# DifferentialPair.net
KiCad netlist of a schematic drawn in Altium Designer
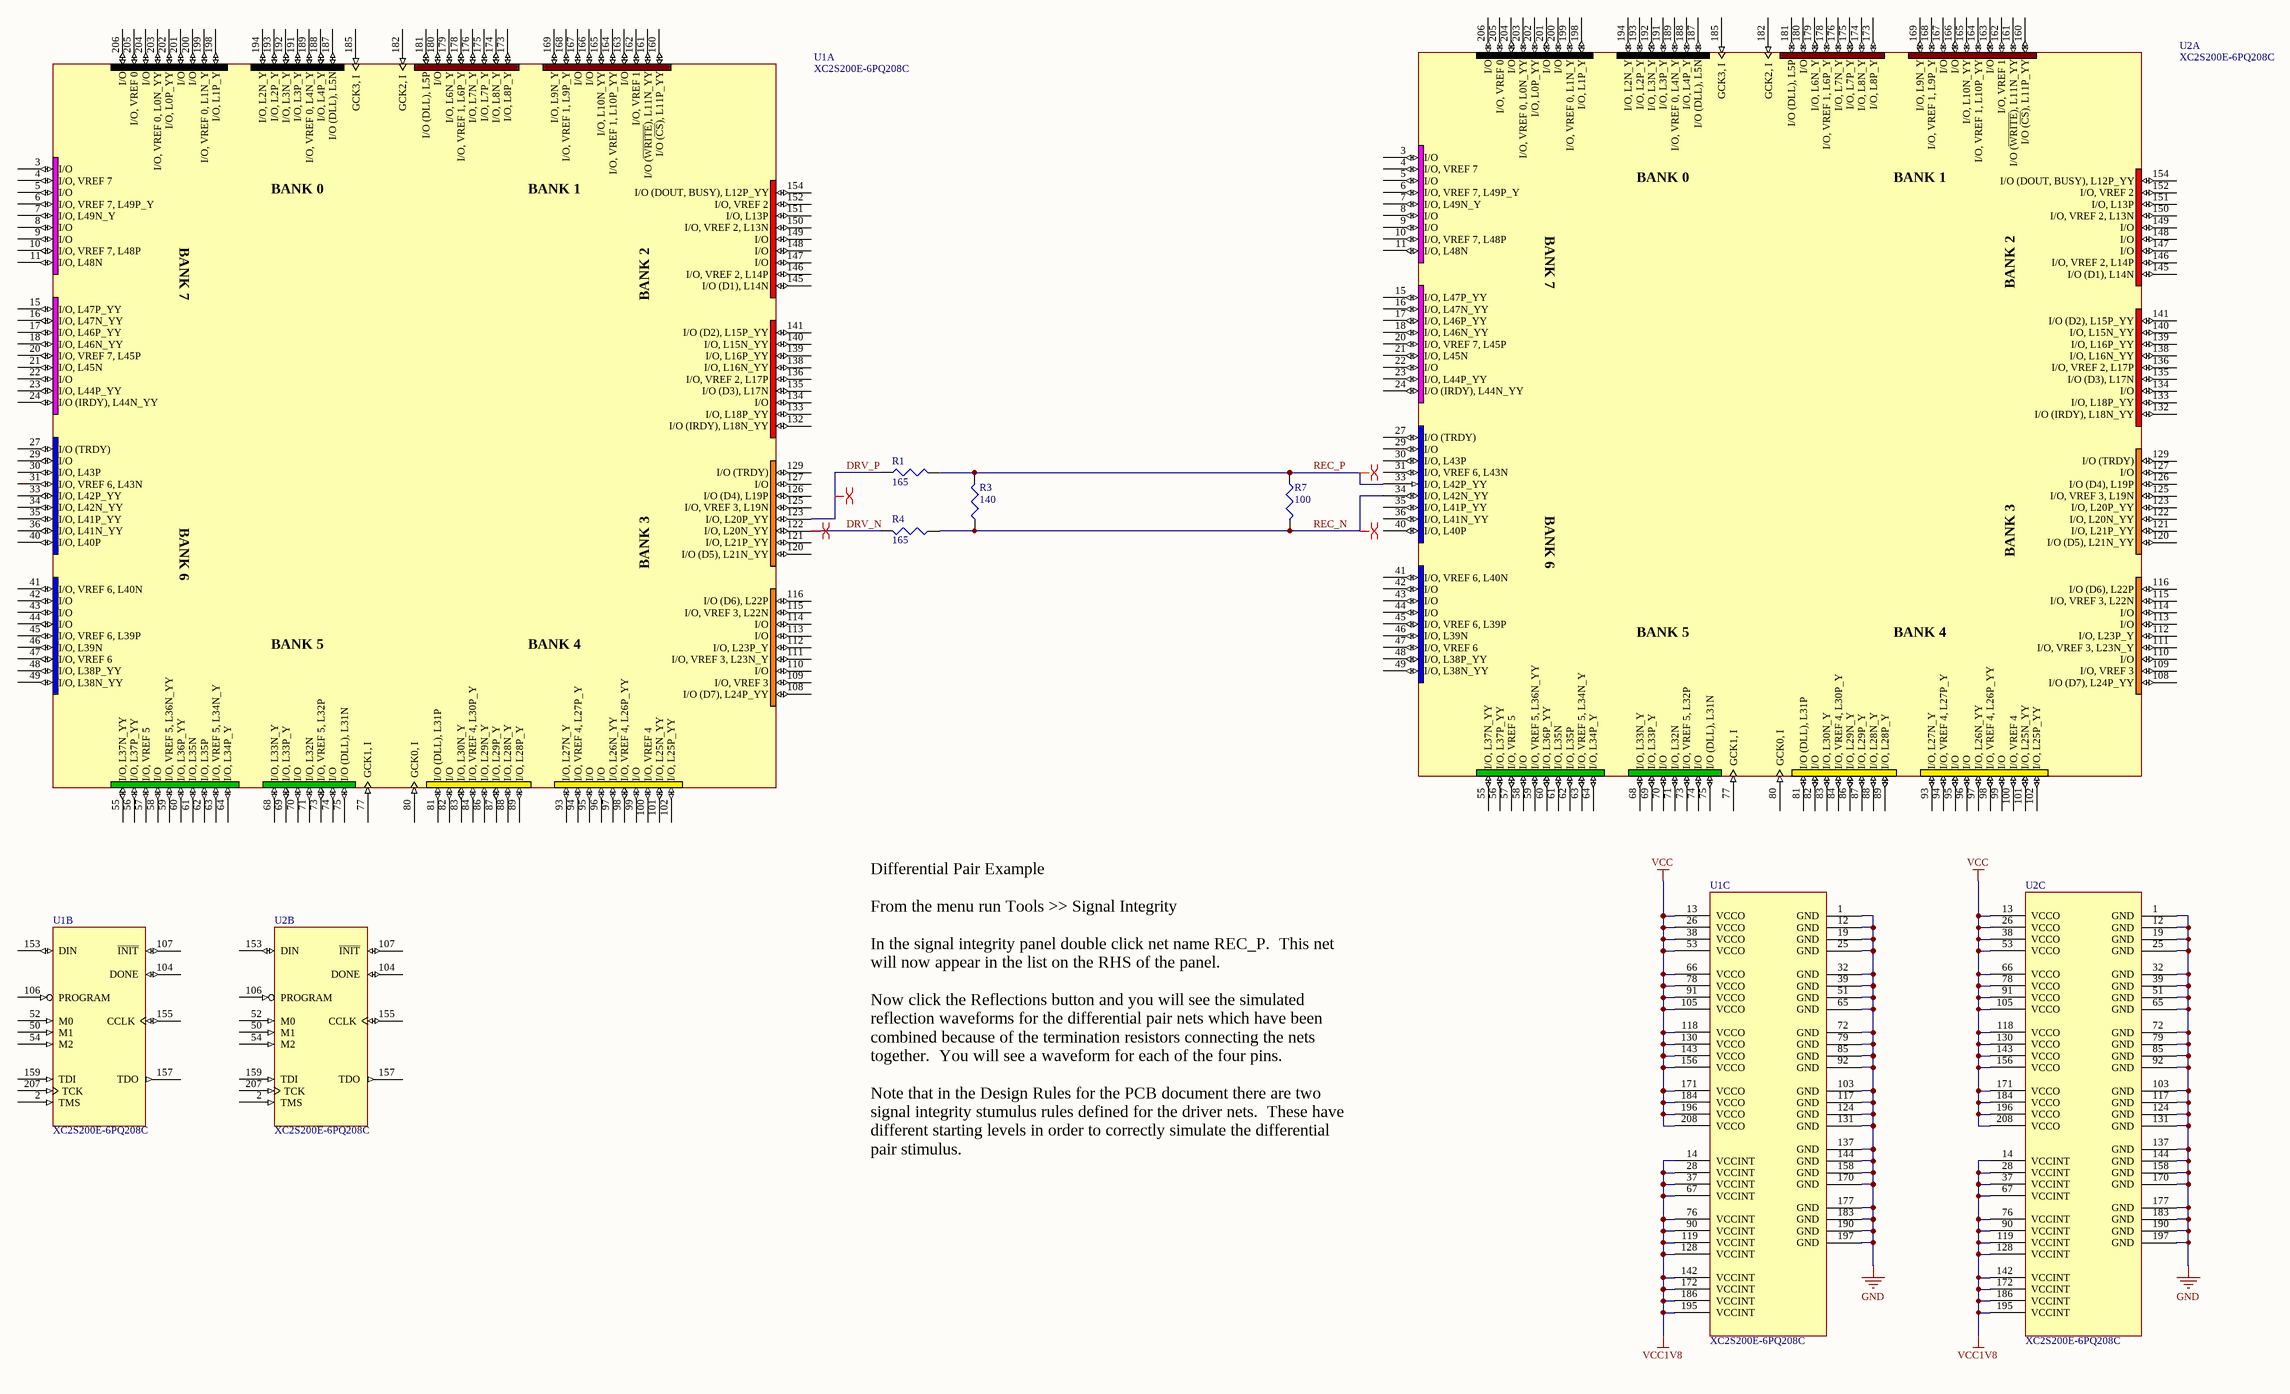
[diagram p0: DifferentialPair.SchDoc]

(export (version "E")
  (design (tool "Eeschema 10.0.6"))
  (components
    (comp (ref "R1")
      (value "165")
      (footprint "J1-0603")
      (description "Resistor")
      (fields (field (name "Comment") "Res3") (field (name "PUBLISHER") "Altium Limited"))
      (libsource (lib "Miscellaneous Devices") (part "Res3"))
    )
    (comp (ref "R3")
      (value "140")
      (footprint "J1-0603")
      (description "Resistor")
      (fields (field (name "Comment") "Res3") (field (name "PUBLISHER") "Altium Limited"))
      (libsource (lib "Miscellaneous Devices") (part "Res3"))
    )
    (comp (ref "R4")
      (value "165")
      (footprint "J1-0603")
      (description "Resistor")
      (fields (field (name "Comment") "Res3") (field (name "PUBLISHER") "Altium Limited"))
      (libsource (lib "Miscellaneous Devices") (part "Res3"))
    )
    (comp (ref "R7")
      (value "100")
      (footprint "J1-0603")
      (description "Resistor")
      (fields (field (name "Comment") "Res3") (field (name "PUBLISHER") "Altium Limited"))
      (libsource (lib "Miscellaneous Devices") (part "Res3"))
    )
    (comp (ref "U1")
      (value "XC2S200E-6PQ208C")
      (footprint "PQ208")
      (description "Spartan-IIE 1.8V FPGA, 208-Pin PQFP, Standard Performance, Commercial Grade")
      (fields (field (name "PUBLISHER") "Altium Limited"))
      (libsource (lib "Xilinx Spartan-IIE") (part "XC2S200E-6PQ208C"))
    )
    (comp (ref "U2")
      (value "XC2S200E-6PQ208C")
      (footprint "PQ208")
      (description "Spartan-IIE 1.8V FPGA, 208-Pin PQFP, Standard Performance, Commercial Grade")
      (fields (field (name "PUBLISHER") "Altium Limited"))
      (libsource (lib "Xilinx Spartan-IIE") (part "XC2S200E-6PQ208C"))
    )
  )
  (nets
    (net (code "1") (name "/DRV_N") (class "Default")
      (node (ref "R4") (pin "2") (pinfunction "2_2") (pintype "passive"))
      (node (ref "U1") (pin "122") (pinfunction "I/O,_L20N_YY_122") (pintype "bidirectional"))
    )
    (net (code "2") (name "/DRV_P") (class "Default")
      (node (ref "R1") (pin "1") (pinfunction "1_1") (pintype "passive"))
      (node (ref "U1") (pin "123") (pinfunction "I/O,_L20P_YY_123") (pintype "bidirectional"))
    )
    (net (code "3") (name "/REC_N") (class "Default")
      (node (ref "R3") (pin "1") (pinfunction "1_1") (pintype "passive"))
      (node (ref "R4") (pin "1") (pinfunction "1_1") (pintype "passive"))
      (node (ref "R7") (pin "2") (pinfunction "2_2") (pintype "passive"))
      (node (ref "U2") (pin "34") (pinfunction "I/O,_L42N_YY_34") (pintype "bidirectional"))
    )
    (net (code "4") (name "/REC_P") (class "Default")
      (node (ref "R1") (pin "2") (pinfunction "2_2") (pintype "passive"))
      (node (ref "R3") (pin "2") (pinfunction "2_2") (pintype "passive"))
      (node (ref "R7") (pin "1") (pinfunction "1_1") (pintype "passive"))
      (node (ref "U2") (pin "33") (pinfunction "I/O,_L42P_YY_33") (pintype "bidirectional"))
    )
    (net (code "5") (name "GND") (class "Default")
      (node (ref "U1") (pin "1") (pinfunction "GND_1") (pintype "power_in"))
      (node (ref "U1") (pin "103") (pinfunction "GND_103") (pintype "power_in"))
      (node (ref "U1") (pin "117") (pinfunction "GND_117") (pintype "power_in"))
      (node (ref "U1") (pin "12") (pinfunction "GND_12") (pintype "power_in"))
      (node (ref "U1") (pin "124") (pinfunction "GND_124") (pintype "power_in"))
      (node (ref "U1") (pin "131") (pinfunction "GND_131") (pintype "power_in"))
      (node (ref "U1") (pin "137") (pinfunction "GND_137") (pintype "power_in"))
      (node (ref "U1") (pin "144") (pinfunction "GND_144") (pintype "power_in"))
      (node (ref "U1") (pin "158") (pinfunction "GND_158") (pintype "power_in"))
      (node (ref "U1") (pin "170") (pinfunction "GND_170") (pintype "power_in"))
      (node (ref "U1") (pin "177") (pinfunction "GND_177") (pintype "power_in"))
      (node (ref "U1") (pin "183") (pinfunction "GND_183") (pintype "power_in"))
      (node (ref "U1") (pin "19") (pinfunction "GND_19") (pintype "power_in"))
      (node (ref "U1") (pin "190") (pinfunction "GND_190") (pintype "power_in"))
      (node (ref "U1") (pin "197") (pinfunction "GND_197") (pintype "power_in"))
      (node (ref "U1") (pin "25") (pinfunction "GND_25") (pintype "power_in"))
      (node (ref "U1") (pin "32") (pinfunction "GND_32") (pintype "power_in"))
      (node (ref "U1") (pin "39") (pinfunction "GND_39") (pintype "power_in"))
      (node (ref "U1") (pin "51") (pinfunction "GND_51") (pintype "power_in"))
      (node (ref "U1") (pin "65") (pinfunction "GND_65") (pintype "power_in"))
      (node (ref "U1") (pin "72") (pinfunction "GND_72") (pintype "power_in"))
      (node (ref "U1") (pin "79") (pinfunction "GND_79") (pintype "power_in"))
      (node (ref "U1") (pin "85") (pinfunction "GND_85") (pintype "power_in"))
      (node (ref "U1") (pin "92") (pinfunction "GND_92") (pintype "power_in"))
      (node (ref "U2") (pin "1") (pinfunction "GND_1") (pintype "power_in"))
      (node (ref "U2") (pin "103") (pinfunction "GND_103") (pintype "power_in"))
      (node (ref "U2") (pin "117") (pinfunction "GND_117") (pintype "power_in"))
      (node (ref "U2") (pin "12") (pinfunction "GND_12") (pintype "power_in"))
      (node (ref "U2") (pin "124") (pinfunction "GND_124") (pintype "power_in"))
      (node (ref "U2") (pin "131") (pinfunction "GND_131") (pintype "power_in"))
      (node (ref "U2") (pin "137") (pinfunction "GND_137") (pintype "power_in"))
      (node (ref "U2") (pin "144") (pinfunction "GND_144") (pintype "power_in"))
      (node (ref "U2") (pin "158") (pinfunction "GND_158") (pintype "power_in"))
      (node (ref "U2") (pin "170") (pinfunction "GND_170") (pintype "power_in"))
      (node (ref "U2") (pin "177") (pinfunction "GND_177") (pintype "power_in"))
      (node (ref "U2") (pin "183") (pinfunction "GND_183") (pintype "power_in"))
      (node (ref "U2") (pin "19") (pinfunction "GND_19") (pintype "power_in"))
      (node (ref "U2") (pin "190") (pinfunction "GND_190") (pintype "power_in"))
      (node (ref "U2") (pin "197") (pinfunction "GND_197") (pintype "power_in"))
      (node (ref "U2") (pin "25") (pinfunction "GND_25") (pintype "power_in"))
      (node (ref "U2") (pin "32") (pinfunction "GND_32") (pintype "power_in"))
      (node (ref "U2") (pin "39") (pinfunction "GND_39") (pintype "power_in"))
      (node (ref "U2") (pin "51") (pinfunction "GND_51") (pintype "power_in"))
      (node (ref "U2") (pin "65") (pinfunction "GND_65") (pintype "power_in"))
      (node (ref "U2") (pin "72") (pinfunction "GND_72") (pintype "power_in"))
      (node (ref "U2") (pin "79") (pinfunction "GND_79") (pintype "power_in"))
      (node (ref "U2") (pin "85") (pinfunction "GND_85") (pintype "power_in"))
      (node (ref "U2") (pin "92") (pinfunction "GND_92") (pintype "power_in"))
    )
    (net (code "6") (name "VCC") (class "Default")
      (node (ref "U1") (pin "105") (pinfunction "VCCO_105") (pintype "power_in"))
      (node (ref "U1") (pin "118") (pinfunction "VCCO_118") (pintype "power_in"))
      (node (ref "U1") (pin "13") (pinfunction "VCCO_13") (pintype "power_in"))
      (node (ref "U1") (pin "130") (pinfunction "VCCO_130") (pintype "power_in"))
      (node (ref "U1") (pin "143") (pinfunction "VCCO_143") (pintype "power_in"))
      (node (ref "U1") (pin "156") (pinfunction "VCCO_156") (pintype "power_in"))
      (node (ref "U1") (pin "171") (pinfunction "VCCO_171") (pintype "power_in"))
      (node (ref "U1") (pin "184") (pinfunction "VCCO_184") (pintype "power_in"))
      (node (ref "U1") (pin "196") (pinfunction "VCCO_196") (pintype "power_in"))
      (node (ref "U1") (pin "208") (pinfunction "VCCO_208") (pintype "power_in"))
      (node (ref "U1") (pin "26") (pinfunction "VCCO_26") (pintype "power_in"))
      (node (ref "U1") (pin "38") (pinfunction "VCCO_38") (pintype "power_in"))
      (node (ref "U1") (pin "53") (pinfunction "VCCO_53") (pintype "power_in"))
      (node (ref "U1") (pin "66") (pinfunction "VCCO_66") (pintype "power_in"))
      (node (ref "U1") (pin "78") (pinfunction "VCCO_78") (pintype "power_in"))
      (node (ref "U1") (pin "91") (pinfunction "VCCO_91") (pintype "power_in"))
      (node (ref "U2") (pin "105") (pinfunction "VCCO_105") (pintype "power_in"))
      (node (ref "U2") (pin "118") (pinfunction "VCCO_118") (pintype "power_in"))
      (node (ref "U2") (pin "13") (pinfunction "VCCO_13") (pintype "power_in"))
      (node (ref "U2") (pin "130") (pinfunction "VCCO_130") (pintype "power_in"))
      (node (ref "U2") (pin "143") (pinfunction "VCCO_143") (pintype "power_in"))
      (node (ref "U2") (pin "156") (pinfunction "VCCO_156") (pintype "power_in"))
      (node (ref "U2") (pin "171") (pinfunction "VCCO_171") (pintype "power_in"))
      (node (ref "U2") (pin "184") (pinfunction "VCCO_184") (pintype "power_in"))
      (node (ref "U2") (pin "196") (pinfunction "VCCO_196") (pintype "power_in"))
      (node (ref "U2") (pin "208") (pinfunction "VCCO_208") (pintype "power_in"))
      (node (ref "U2") (pin "26") (pinfunction "VCCO_26") (pintype "power_in"))
      (node (ref "U2") (pin "38") (pinfunction "VCCO_38") (pintype "power_in"))
      (node (ref "U2") (pin "53") (pinfunction "VCCO_53") (pintype "power_in"))
      (node (ref "U2") (pin "66") (pinfunction "VCCO_66") (pintype "power_in"))
      (node (ref "U2") (pin "78") (pinfunction "VCCO_78") (pintype "power_in"))
      (node (ref "U2") (pin "91") (pinfunction "VCCO_91") (pintype "power_in"))
    )
    (net (code "7") (name "VCC1V8") (class "Default")
      (node (ref "U1") (pin "119") (pinfunction "VCCINT_119") (pintype "power_in"))
      (node (ref "U1") (pin "128") (pinfunction "VCCINT_128") (pintype "power_in"))
      (node (ref "U1") (pin "14") (pinfunction "VCCINT_14") (pintype "power_in"))
      (node (ref "U1") (pin "142") (pinfunction "VCCINT_142") (pintype "power_in"))
      (node (ref "U1") (pin "172") (pinfunction "VCCINT_172") (pintype "power_in"))
      (node (ref "U1") (pin "186") (pinfunction "VCCINT_186") (pintype "power_in"))
      (node (ref "U1") (pin "195") (pinfunction "VCCINT_195") (pintype "power_in"))
      (node (ref "U1") (pin "28") (pinfunction "VCCINT_28") (pintype "power_in"))
      (node (ref "U1") (pin "37") (pinfunction "VCCINT_37") (pintype "power_in"))
      (node (ref "U1") (pin "67") (pinfunction "VCCINT_67") (pintype "power_in"))
      (node (ref "U1") (pin "76") (pinfunction "VCCINT_76") (pintype "power_in"))
      (node (ref "U1") (pin "90") (pinfunction "VCCINT_90") (pintype "power_in"))
      (node (ref "U2") (pin "119") (pinfunction "VCCINT_119") (pintype "power_in"))
      (node (ref "U2") (pin "128") (pinfunction "VCCINT_128") (pintype "power_in"))
      (node (ref "U2") (pin "14") (pinfunction "VCCINT_14") (pintype "power_in"))
      (node (ref "U2") (pin "142") (pinfunction "VCCINT_142") (pintype "power_in"))
      (node (ref "U2") (pin "172") (pinfunction "VCCINT_172") (pintype "power_in"))
      (node (ref "U2") (pin "186") (pinfunction "VCCINT_186") (pintype "power_in"))
      (node (ref "U2") (pin "195") (pinfunction "VCCINT_195") (pintype "power_in"))
      (node (ref "U2") (pin "28") (pinfunction "VCCINT_28") (pintype "power_in"))
      (node (ref "U2") (pin "37") (pinfunction "VCCINT_37") (pintype "power_in"))
      (node (ref "U2") (pin "67") (pinfunction "VCCINT_67") (pintype "power_in"))
      (node (ref "U2") (pin "76") (pinfunction "VCCINT_76") (pintype "power_in"))
      (node (ref "U2") (pin "90") (pinfunction "VCCINT_90") (pintype "power_in"))
    )
    (net (code "8") (name "unconnected-(U1A-GCK0,_I-Pad80)") (class "Default")
      (node (ref "U1") (pin "80") (pinfunction "GCK0,_I_80") (pintype "input"))
    )
    (net (code "9") (name "unconnected-(U1A-GCK1,_I-Pad77)") (class "Default")
      (node (ref "U1") (pin "77") (pinfunction "GCK1,_I_77") (pintype "input"))
    )
    (net (code "10") (name "unconnected-(U1A-GCK2,_I-Pad182)") (class "Default")
      (node (ref "U1") (pin "182") (pinfunction "GCK2,_I_182") (pintype "input"))
    )
    (net (code "11") (name "unconnected-(U1A-GCK3,_I-Pad185)") (class "Default")
      (node (ref "U1") (pin "185") (pinfunction "GCK3,_I_185") (pintype "input"))
    )
    (net (code "12") (name "unconnected-(U1A-I{slash}O,_L0P_YY-Pad202)") (class "Default")
      (node (ref "U1") (pin "202") (pinfunction "I/O,_L0P_YY_202") (pintype "bidirectional"))
    )
    (net (code "13") (name "unconnected-(U1A-I{slash}O,_L1P_Y-Pad198)") (class "Default")
      (node (ref "U1") (pin "198") (pinfunction "I/O,_L1P_Y_198") (pintype "bidirectional"))
    )
    (net (code "14") (name "unconnected-(U1A-I{slash}O,_L2N_Y-Pad194)") (class "Default")
      (node (ref "U1") (pin "194") (pinfunction "I/O,_L2N_Y_194") (pintype "bidirectional"))
    )
    (net (code "15") (name "unconnected-(U1A-I{slash}O,_L2P_Y-Pad193)") (class "Default")
      (node (ref "U1") (pin "193") (pinfunction "I/O,_L2P_Y_193") (pintype "bidirectional"))
    )
    (net (code "16") (name "unconnected-(U1A-I{slash}O,_L3N_Y-Pad192)") (class "Default")
      (node (ref "U1") (pin "192") (pinfunction "I/O,_L3N_Y_192") (pintype "bidirectional"))
    )
    (net (code "17") (name "unconnected-(U1A-I{slash}O,_L3P_Y-Pad191)") (class "Default")
      (node (ref "U1") (pin "191") (pinfunction "I/O,_L3P_Y_191") (pintype "bidirectional"))
    )
    (net (code "18") (name "unconnected-(U1A-I{slash}O,_L4P_Y-Pad188)") (class "Default")
      (node (ref "U1") (pin "188") (pinfunction "I/O,_L4P_Y_188") (pintype "bidirectional"))
    )
    (net (code "19") (name "unconnected-(U1A-I{slash}O,_L6N_Y-Pad179)") (class "Default")
      (node (ref "U1") (pin "179") (pinfunction "I/O,_L6N_Y_179") (pintype "bidirectional"))
    )
    (net (code "20") (name "unconnected-(U1A-I{slash}O,_L7N_Y-Pad176)") (class "Default")
      (node (ref "U1") (pin "176") (pinfunction "I/O,_L7N_Y_176") (pintype "bidirectional"))
    )
    (net (code "21") (name "unconnected-(U1A-I{slash}O,_L7P_Y-Pad175)") (class "Default")
      (node (ref "U1") (pin "175") (pinfunction "I/O,_L7P_Y_175") (pintype "bidirectional"))
    )
    (net (code "22") (name "unconnected-(U1A-I{slash}O,_L8N_Y-Pad174)") (class "Default")
      (node (ref "U1") (pin "174") (pinfunction "I/O,_L8N_Y_174") (pintype "bidirectional"))
    )
    (net (code "23") (name "unconnected-(U1A-I{slash}O,_L8P_Y-Pad173)") (class "Default")
      (node (ref "U1") (pin "173") (pinfunction "I/O,_L8P_Y_173") (pintype "bidirectional"))
    )
    (net (code "24") (name "unconnected-(U1A-I{slash}O,_L9N_Y-Pad169)") (class "Default")
      (node (ref "U1") (pin "169") (pinfunction "I/O,_L9N_Y_169") (pintype "bidirectional"))
    )
    (net (code "25") (name "unconnected-(U1A-I{slash}O,_L10N_YY-Pad165)") (class "Default")
      (node (ref "U1") (pin "165") (pinfunction "I/O,_L10N_YY_165") (pintype "bidirectional"))
    )
    (net (code "26") (name "unconnected-(U1A-I{slash}O,_L13P-Pad151)") (class "Default")
      (node (ref "U1") (pin "151") (pinfunction "I/O,_L13P_151") (pintype "bidirectional"))
    )
    (net (code "27") (name "unconnected-(U1A-I{slash}O,_L15N_YY-Pad140)") (class "Default")
      (node (ref "U1") (pin "140") (pinfunction "I/O,_L15N_YY_140") (pintype "bidirectional"))
    )
    (net (code "28") (name "unconnected-(U1A-I{slash}O,_L16N_YY-Pad138)") (class "Default")
      (node (ref "U1") (pin "138") (pinfunction "I/O,_L16N_YY_138") (pintype "bidirectional"))
    )
    (net (code "29") (name "unconnected-(U1A-I{slash}O,_L16P_YY-Pad139)") (class "Default")
      (node (ref "U1") (pin "139") (pinfunction "I/O,_L16P_YY_139") (pintype "bidirectional"))
    )
    (net (code "30") (name "unconnected-(U1A-I{slash}O,_L18P_YY-Pad133)") (class "Default")
      (node (ref "U1") (pin "133") (pinfunction "I/O,_L18P_YY_133") (pintype "bidirectional"))
    )
    (net (code "31") (name "unconnected-(U1A-I{slash}O,_L21P_YY-Pad121)") (class "Default")
      (node (ref "U1") (pin "121") (pinfunction "I/O,_L21P_YY_121") (pintype "bidirectional"))
    )
    (net (code "32") (name "unconnected-(U1A-I{slash}O,_L23P_Y-Pad112)") (class "Default")
      (node (ref "U1") (pin "112") (pinfunction "I/O,_L23P_Y_112") (pintype "bidirectional"))
    )
    (net (code "33") (name "unconnected-(U1A-I{slash}O,_L25N_YY-Pad101)") (class "Default")
      (node (ref "U1") (pin "101") (pinfunction "I/O,_L25N_YY_101") (pintype "bidirectional"))
    )
    (net (code "34") (name "unconnected-(U1A-I{slash}O,_L25P_YY-Pad102)") (class "Default")
      (node (ref "U1") (pin "102") (pinfunction "I/O,_L25P_YY_102") (pintype "bidirectional"))
    )
    (net (code "35") (name "unconnected-(U1A-I{slash}O,_L26N_YY-Pad97)") (class "Default")
      (node (ref "U1") (pin "97") (pinfunction "I/O,_L26N_YY_97") (pintype "bidirectional"))
    )
    (net (code "36") (name "unconnected-(U1A-I{slash}O,_L27N_Y-Pad93)") (class "Default")
      (node (ref "U1") (pin "93") (pinfunction "I/O,_L27N_Y_93") (pintype "bidirectional"))
    )
    (net (code "37") (name "unconnected-(U1A-I{slash}O,_L28N_Y-Pad88)") (class "Default")
      (node (ref "U1") (pin "88") (pinfunction "I/O,_L28N_Y_88") (pintype "bidirectional"))
    )
    (net (code "38") (name "unconnected-(U1A-I{slash}O,_L28P_Y-Pad89)") (class "Default")
      (node (ref "U1") (pin "89") (pinfunction "I/O,_L28P_Y_89") (pintype "bidirectional"))
    )
    (net (code "39") (name "unconnected-(U1A-I{slash}O,_L29N_Y-Pad86)") (class "Default")
      (node (ref "U1") (pin "86") (pinfunction "I/O,_L29N_Y_86") (pintype "bidirectional"))
    )
    (net (code "40") (name "unconnected-(U1A-I{slash}O,_L29P_Y-Pad87)") (class "Default")
      (node (ref "U1") (pin "87") (pinfunction "I/O,_L29P_Y_87") (pintype "bidirectional"))
    )
    (net (code "41") (name "unconnected-(U1A-I{slash}O,_L30N_Y-Pad83)") (class "Default")
      (node (ref "U1") (pin "83") (pinfunction "I/O,_L30N_Y_83") (pintype "bidirectional"))
    )
    (net (code "42") (name "unconnected-(U1A-I{slash}O,_L32N-Pad71)") (class "Default")
      (node (ref "U1") (pin "71") (pinfunction "I/O,_L32N_71") (pintype "bidirectional"))
    )
    (net (code "43") (name "unconnected-(U1A-I{slash}O,_L33N_Y-Pad68)") (class "Default")
      (node (ref "U1") (pin "68") (pinfunction "I/O,_L33N_Y_68") (pintype "bidirectional"))
    )
    (net (code "44") (name "unconnected-(U1A-I{slash}O,_L33P_Y-Pad69)") (class "Default")
      (node (ref "U1") (pin "69") (pinfunction "I/O,_L33P_Y_69") (pintype "bidirectional"))
    )
    (net (code "45") (name "unconnected-(U1A-I{slash}O,_L34P_Y-Pad64)") (class "Default")
      (node (ref "U1") (pin "64") (pinfunction "I/O,_L34P_Y_64") (pintype "bidirectional"))
    )
    (net (code "46") (name "unconnected-(U1A-I{slash}O,_L35N-Pad61)") (class "Default")
      (node (ref "U1") (pin "61") (pinfunction "I/O,_L35N_61") (pintype "bidirectional"))
    )
    (net (code "47") (name "unconnected-(U1A-I{slash}O,_L35P-Pad62)") (class "Default")
      (node (ref "U1") (pin "62") (pinfunction "I/O,_L35P_62") (pintype "bidirectional"))
    )
    (net (code "48") (name "unconnected-(U1A-I{slash}O,_L36P_YY-Pad60)") (class "Default")
      (node (ref "U1") (pin "60") (pinfunction "I/O,_L36P_YY_60") (pintype "bidirectional"))
    )
    (net (code "49") (name "unconnected-(U1A-I{slash}O,_L37N_YY-Pad55)") (class "Default")
      (node (ref "U1") (pin "55") (pinfunction "I/O,_L37N_YY_55") (pintype "bidirectional"))
    )
    (net (code "50") (name "unconnected-(U1A-I{slash}O,_L37P_YY-Pad56)") (class "Default")
      (node (ref "U1") (pin "56") (pinfunction "I/O,_L37P_YY_56") (pintype "bidirectional"))
    )
    (net (code "51") (name "unconnected-(U1A-I{slash}O,_L38N_YY-Pad49)") (class "Default")
      (node (ref "U1") (pin "49") (pinfunction "I/O,_L38N_YY_49") (pintype "bidirectional"))
    )
    (net (code "52") (name "unconnected-(U1A-I{slash}O,_L38P_YY-Pad48)") (class "Default")
      (node (ref "U1") (pin "48") (pinfunction "I/O,_L38P_YY_48") (pintype "bidirectional"))
    )
    (net (code "53") (name "unconnected-(U1A-I{slash}O,_L39N-Pad46)") (class "Default")
      (node (ref "U1") (pin "46") (pinfunction "I/O,_L39N_46") (pintype "bidirectional"))
    )
    (net (code "54") (name "unconnected-(U1A-I{slash}O,_L40P-Pad40)") (class "Default")
      (node (ref "U1") (pin "40") (pinfunction "I/O,_L40P_40") (pintype "bidirectional"))
    )
    (net (code "55") (name "unconnected-(U1A-I{slash}O,_L41N_YY-Pad36)") (class "Default")
      (node (ref "U1") (pin "36") (pinfunction "I/O,_L41N_YY_36") (pintype "bidirectional"))
    )
    (net (code "56") (name "unconnected-(U1A-I{slash}O,_L41P_YY-Pad35)") (class "Default")
      (node (ref "U1") (pin "35") (pinfunction "I/O,_L41P_YY_35") (pintype "bidirectional"))
    )
    (net (code "57") (name "unconnected-(U1A-I{slash}O,_L42N_YY-Pad34)") (class "Default")
      (node (ref "U1") (pin "34") (pinfunction "I/O,_L42N_YY_34") (pintype "bidirectional"))
    )
    (net (code "58") (name "unconnected-(U1A-I{slash}O,_L42P_YY-Pad33)") (class "Default")
      (node (ref "U1") (pin "33") (pinfunction "I/O,_L42P_YY_33") (pintype "bidirectional"))
    )
    (net (code "59") (name "unconnected-(U1A-I{slash}O,_L43P-Pad30)") (class "Default")
      (node (ref "U1") (pin "30") (pinfunction "I/O,_L43P_30") (pintype "bidirectional"))
    )
    (net (code "60") (name "unconnected-(U1A-I{slash}O,_L44P_YY-Pad23)") (class "Default")
      (node (ref "U1") (pin "23") (pinfunction "I/O,_L44P_YY_23") (pintype "bidirectional"))
    )
    (net (code "61") (name "unconnected-(U1A-I{slash}O,_L45N-Pad21)") (class "Default")
      (node (ref "U1") (pin "21") (pinfunction "I/O,_L45N_21") (pintype "bidirectional"))
    )
    (net (code "62") (name "unconnected-(U1A-I{slash}O,_L46N_YY-Pad18)") (class "Default")
      (node (ref "U1") (pin "18") (pinfunction "I/O,_L46N_YY_18") (pintype "bidirectional"))
    )
    (net (code "63") (name "unconnected-(U1A-I{slash}O,_L46P_YY-Pad17)") (class "Default")
      (node (ref "U1") (pin "17") (pinfunction "I/O,_L46P_YY_17") (pintype "bidirectional"))
    )
    (net (code "64") (name "unconnected-(U1A-I{slash}O,_L47N_YY-Pad16)") (class "Default")
      (node (ref "U1") (pin "16") (pinfunction "I/O,_L47N_YY_16") (pintype "bidirectional"))
    )
    (net (code "65") (name "unconnected-(U1A-I{slash}O,_L47P_YY-Pad15)") (class "Default")
      (node (ref "U1") (pin "15") (pinfunction "I/O,_L47P_YY_15") (pintype "bidirectional"))
    )
    (net (code "66") (name "unconnected-(U1A-I{slash}O,_L48N-Pad11)") (class "Default")
      (node (ref "U1") (pin "11") (pinfunction "I/O,_L48N_11") (pintype "bidirectional"))
    )
    (net (code "67") (name "unconnected-(U1A-I{slash}O,_L49N_Y-Pad7)") (class "Default")
      (node (ref "U1") (pin "7") (pinfunction "I/O,_L49N_Y_7") (pintype "bidirectional"))
    )
    (net (code "68") (name "unconnected-(U1A-I{slash}O,_VREF_0,_L0N_YY-Pad203)") (class "Default")
      (node (ref "U1") (pin "203") (pinfunction "I/O,_VREF_0,_L0N_YY_203") (pintype "bidirectional"))
    )
    (net (code "69") (name "unconnected-(U1A-I{slash}O,_VREF_0,_L1N_Y-Pad199)") (class "Default")
      (node (ref "U1") (pin "199") (pinfunction "I/O,_VREF_0,_L1N_Y_199") (pintype "bidirectional"))
    )
    (net (code "70") (name "unconnected-(U1A-I{slash}O,_VREF_0,_L4N_Y-Pad189)") (class "Default")
      (node (ref "U1") (pin "189") (pinfunction "I/O,_VREF_0,_L4N_Y_189") (pintype "bidirectional"))
    )
    (net (code "71") (name "unconnected-(U1A-I{slash}O,_VREF_0-Pad205)") (class "Default")
      (node (ref "U1") (pin "205") (pinfunction "I/O,_VREF_0_205") (pintype "bidirectional"))
    )
    (net (code "72") (name "unconnected-(U1A-I{slash}O,_VREF_1,_L6P_Y-Pad178)") (class "Default")
      (node (ref "U1") (pin "178") (pinfunction "I/O,_VREF_1,_L6P_Y_178") (pintype "bidirectional"))
    )
    (net (code "73") (name "unconnected-(U1A-I{slash}O,_VREF_1,_L9P_Y-Pad168)") (class "Default")
      (node (ref "U1") (pin "168") (pinfunction "I/O,_VREF_1,_L9P_Y_168") (pintype "bidirectional"))
    )
    (net (code "74") (name "unconnected-(U1A-I{slash}O,_VREF_1,_L10P_YY-Pad164)") (class "Default")
      (node (ref "U1") (pin "164") (pinfunction "I/O,_VREF_1,_L10P_YY_164") (pintype "bidirectional"))
    )
    (net (code "75") (name "unconnected-(U1A-I{slash}O,_VREF_1-Pad162)") (class "Default")
      (node (ref "U1") (pin "162") (pinfunction "I/O,_VREF_1_162") (pintype "bidirectional"))
    )
    (net (code "76") (name "unconnected-(U1A-I{slash}O,_VREF_2,_L13N-Pad150)") (class "Default")
      (node (ref "U1") (pin "150") (pinfunction "I/O,_VREF_2,_L13N_150") (pintype "bidirectional"))
    )
    (net (code "77") (name "unconnected-(U1A-I{slash}O,_VREF_2,_L14P-Pad146)") (class "Default")
      (node (ref "U1") (pin "146") (pinfunction "I/O,_VREF_2,_L14P_146") (pintype "bidirectional"))
    )
    (net (code "78") (name "unconnected-(U1A-I{slash}O,_VREF_2,_L17P-Pad136)") (class "Default")
      (node (ref "U1") (pin "136") (pinfunction "I/O,_VREF_2,_L17P_136") (pintype "bidirectional"))
    )
    (net (code "79") (name "unconnected-(U1A-I{slash}O,_VREF_2-Pad152)") (class "Default")
      (node (ref "U1") (pin "152") (pinfunction "I/O,_VREF_2_152") (pintype "bidirectional"))
    )
    (net (code "80") (name "unconnected-(U1A-I{slash}O,_VREF_3,_L19N-Pad125)") (class "Default")
      (node (ref "U1") (pin "125") (pinfunction "I/O,_VREF_3,_L19N_125") (pintype "bidirectional"))
    )
    (net (code "81") (name "unconnected-(U1A-I{slash}O,_VREF_3,_L22N-Pad115)") (class "Default")
      (node (ref "U1") (pin "115") (pinfunction "I/O,_VREF_3,_L22N_115") (pintype "bidirectional"))
    )
    (net (code "82") (name "unconnected-(U1A-I{slash}O,_VREF_3,_L23N_Y-Pad111)") (class "Default")
      (node (ref "U1") (pin "111") (pinfunction "I/O,_VREF_3,_L23N_Y_111") (pintype "bidirectional"))
    )
    (net (code "83") (name "unconnected-(U1A-I{slash}O,_VREF_3-Pad109)") (class "Default")
      (node (ref "U1") (pin "109") (pinfunction "I/O,_VREF_3_109") (pintype "bidirectional"))
    )
    (net (code "84") (name "unconnected-(U1A-I{slash}O,_VREF_4,_L26P_YY-Pad98)") (class "Default")
      (node (ref "U1") (pin "98") (pinfunction "I/O,_VREF_4,_L26P_YY_98") (pintype "bidirectional"))
    )
    (net (code "85") (name "unconnected-(U1A-I{slash}O,_VREF_4,_L27P_Y-Pad94)") (class "Default")
      (node (ref "U1") (pin "94") (pinfunction "I/O,_VREF_4,_L27P_Y_94") (pintype "bidirectional"))
    )
    (net (code "86") (name "unconnected-(U1A-I{slash}O,_VREF_4,_L30P_Y-Pad84)") (class "Default")
      (node (ref "U1") (pin "84") (pinfunction "I/O,_VREF_4,_L30P_Y_84") (pintype "bidirectional"))
    )
    (net (code "87") (name "unconnected-(U1A-I{slash}O,_VREF_4-Pad100)") (class "Default")
      (node (ref "U1") (pin "100") (pinfunction "I/O,_VREF_4_100") (pintype "bidirectional"))
    )
    (net (code "88") (name "unconnected-(U1A-I{slash}O,_VREF_5,_L32P-Pad73)") (class "Default")
      (node (ref "U1") (pin "73") (pinfunction "I/O,_VREF_5,_L32P_73") (pintype "bidirectional"))
    )
    (net (code "89") (name "unconnected-(U1A-I{slash}O,_VREF_5,_L34N_Y-Pad63)") (class "Default")
      (node (ref "U1") (pin "63") (pinfunction "I/O,_VREF_5,_L34N_Y_63") (pintype "bidirectional"))
    )
    (net (code "90") (name "unconnected-(U1A-I{slash}O,_VREF_5,_L36N_YY-Pad59)") (class "Default")
      (node (ref "U1") (pin "59") (pinfunction "I/O,_VREF_5,_L36N_YY_59") (pintype "bidirectional"))
    )
    (net (code "91") (name "unconnected-(U1A-I{slash}O,_VREF_5-Pad57)") (class "Default")
      (node (ref "U1") (pin "57") (pinfunction "I/O,_VREF_5_57") (pintype "bidirectional"))
    )
    (net (code "92") (name "unconnected-(U1A-I{slash}O,_VREF_6,_L39P-Pad45)") (class "Default")
      (node (ref "U1") (pin "45") (pinfunction "I/O,_VREF_6,_L39P_45") (pintype "bidirectional"))
    )
    (net (code "93") (name "unconnected-(U1A-I{slash}O,_VREF_6,_L40N-Pad41)") (class "Default")
      (node (ref "U1") (pin "41") (pinfunction "I/O,_VREF_6,_L40N_41") (pintype "bidirectional"))
    )
    (net (code "94") (name "unconnected-(U1A-I{slash}O,_VREF_6,_L43N-Pad31)") (class "Default")
      (node (ref "U1") (pin "31") (pinfunction "I/O,_VREF_6,_L43N_31") (pintype "bidirectional"))
    )
    (net (code "95") (name "unconnected-(U1A-I{slash}O,_VREF_6-Pad47)") (class "Default")
      (node (ref "U1") (pin "47") (pinfunction "I/O,_VREF_6_47") (pintype "bidirectional"))
    )
    (net (code "96") (name "unconnected-(U1A-I{slash}O,_VREF_7,_L45P-Pad20)") (class "Default")
      (node (ref "U1") (pin "20") (pinfunction "I/O,_VREF_7,_L45P_20") (pintype "bidirectional"))
    )
    (net (code "97") (name "unconnected-(U1A-I{slash}O,_VREF_7,_L48P-Pad10)") (class "Default")
      (node (ref "U1") (pin "10") (pinfunction "I/O,_VREF_7,_L48P_10") (pintype "bidirectional"))
    )
    (net (code "98") (name "unconnected-(U1A-I{slash}O,_VREF_7,_L49P_Y-Pad6)") (class "Default")
      (node (ref "U1") (pin "6") (pinfunction "I/O,_VREF_7,_L49P_Y_6") (pintype "bidirectional"))
    )
    (net (code "99") (name "unconnected-(U1A-I{slash}O,_VREF_7-Pad4)") (class "Default")
      (node (ref "U1") (pin "4") (pinfunction "I/O,_VREF_7_4") (pintype "bidirectional"))
    )
    (net (code "100") (name "unconnected-(U1A-I{slash}O-Pad3)") (class "Default")
      (node (ref "U1") (pin "3") (pinfunction "I/O_3") (pintype "bidirectional"))
    )
    (net (code "101") (name "unconnected-(U1A-I{slash}O-Pad5)") (class "Default")
      (node (ref "U1") (pin "5") (pinfunction "I/O_5") (pintype "bidirectional"))
    )
    (net (code "102") (name "unconnected-(U1A-I{slash}O-Pad8)") (class "Default")
      (node (ref "U1") (pin "8") (pinfunction "I/O_8") (pintype "bidirectional"))
    )
    (net (code "103") (name "unconnected-(U1A-I{slash}O-Pad9)") (class "Default")
      (node (ref "U1") (pin "9") (pinfunction "I/O_9") (pintype "bidirectional"))
    )
    (net (code "104") (name "unconnected-(U1A-I{slash}O-Pad22)") (class "Default")
      (node (ref "U1") (pin "22") (pinfunction "I/O_22") (pintype "bidirectional"))
    )
    (net (code "105") (name "unconnected-(U1A-I{slash}O-Pad29)") (class "Default")
      (node (ref "U1") (pin "29") (pinfunction "I/O_29") (pintype "bidirectional"))
    )
    (net (code "106") (name "unconnected-(U1A-I{slash}O-Pad42)") (class "Default")
      (node (ref "U1") (pin "42") (pinfunction "I/O_42") (pintype "bidirectional"))
    )
    (net (code "107") (name "unconnected-(U1A-I{slash}O-Pad43)") (class "Default")
      (node (ref "U1") (pin "43") (pinfunction "I/O_43") (pintype "bidirectional"))
    )
    (net (code "108") (name "unconnected-(U1A-I{slash}O-Pad44)") (class "Default")
      (node (ref "U1") (pin "44") (pinfunction "I/O_44") (pintype "bidirectional"))
    )
    (net (code "109") (name "unconnected-(U1A-I{slash}O-Pad58)") (class "Default")
      (node (ref "U1") (pin "58") (pinfunction "I/O_58") (pintype "bidirectional"))
    )
    (net (code "110") (name "unconnected-(U1A-I{slash}O-Pad70)") (class "Default")
      (node (ref "U1") (pin "70") (pinfunction "I/O_70") (pintype "bidirectional"))
    )
    (net (code "111") (name "unconnected-(U1A-I{slash}O-Pad74)") (class "Default")
      (node (ref "U1") (pin "74") (pinfunction "I/O_74") (pintype "bidirectional"))
    )
    (net (code "112") (name "unconnected-(U1A-I{slash}O-Pad82)") (class "Default")
      (node (ref "U1") (pin "82") (pinfunction "I/O_82") (pintype "bidirectional"))
    )
    (net (code "113") (name "unconnected-(U1A-I{slash}O-Pad95)") (class "Default")
      (node (ref "U1") (pin "95") (pinfunction "I/O_95") (pintype "bidirectional"))
    )
    (net (code "114") (name "unconnected-(U1A-I{slash}O-Pad96)") (class "Default")
      (node (ref "U1") (pin "96") (pinfunction "I/O_96") (pintype "bidirectional"))
    )
    (net (code "115") (name "unconnected-(U1A-I{slash}O-Pad99)") (class "Default")
      (node (ref "U1") (pin "99") (pinfunction "I/O_99") (pintype "bidirectional"))
    )
    (net (code "116") (name "unconnected-(U1A-I{slash}O-Pad110)") (class "Default")
      (node (ref "U1") (pin "110") (pinfunction "I/O_110") (pintype "bidirectional"))
    )
    (net (code "117") (name "unconnected-(U1A-I{slash}O-Pad113)") (class "Default")
      (node (ref "U1") (pin "113") (pinfunction "I/O_113") (pintype "bidirectional"))
    )
    (net (code "118") (name "unconnected-(U1A-I{slash}O-Pad114)") (class "Default")
      (node (ref "U1") (pin "114") (pinfunction "I/O_114") (pintype "bidirectional"))
    )
    (net (code "119") (name "unconnected-(U1A-I{slash}O-Pad127)") (class "Default")
      (node (ref "U1") (pin "127") (pinfunction "I/O_127") (pintype "bidirectional"))
    )
    (net (code "120") (name "unconnected-(U1A-I{slash}O-Pad134)") (class "Default")
      (node (ref "U1") (pin "134") (pinfunction "I/O_134") (pintype "bidirectional"))
    )
    (net (code "121") (name "unconnected-(U1A-I{slash}O-Pad147)") (class "Default")
      (node (ref "U1") (pin "147") (pinfunction "I/O_147") (pintype "bidirectional"))
    )
    (net (code "122") (name "unconnected-(U1A-I{slash}O-Pad148)") (class "Default")
      (node (ref "U1") (pin "148") (pinfunction "I/O_148") (pintype "bidirectional"))
    )
    (net (code "123") (name "unconnected-(U1A-I{slash}O-Pad149)") (class "Default")
      (node (ref "U1") (pin "149") (pinfunction "I/O_149") (pintype "bidirectional"))
    )
    (net (code "124") (name "unconnected-(U1A-I{slash}O-Pad163)") (class "Default")
      (node (ref "U1") (pin "163") (pinfunction "I/O_163") (pintype "bidirectional"))
    )
    (net (code "125") (name "unconnected-(U1A-I{slash}O-Pad166)") (class "Default")
      (node (ref "U1") (pin "166") (pinfunction "I/O_166") (pintype "bidirectional"))
    )
    (net (code "126") (name "unconnected-(U1A-I{slash}O-Pad167)") (class "Default")
      (node (ref "U1") (pin "167") (pinfunction "I/O_167") (pintype "bidirectional"))
    )
    (net (code "127") (name "unconnected-(U1A-I{slash}O-Pad180)") (class "Default")
      (node (ref "U1") (pin "180") (pinfunction "I/O_180") (pintype "bidirectional"))
    )
    (net (code "128") (name "unconnected-(U1A-I{slash}O-Pad200)") (class "Default")
      (node (ref "U1") (pin "200") (pinfunction "I/O_200") (pintype "bidirectional"))
    )
    (net (code "129") (name "unconnected-(U1A-I{slash}O-Pad201)") (class "Default")
      (node (ref "U1") (pin "201") (pinfunction "I/O_201") (pintype "bidirectional"))
    )
    (net (code "130") (name "unconnected-(U1A-I{slash}O-Pad204)") (class "Default")
      (node (ref "U1") (pin "204") (pinfunction "I/O_204") (pintype "bidirectional"))
    )
    (net (code "131") (name "unconnected-(U1A-I{slash}O-Pad206)") (class "Default")
      (node (ref "U1") (pin "206") (pinfunction "I/O_206") (pintype "bidirectional"))
    )
    (net (code "132") (name "unconnected-(U1A-I{slash}O_(D1),_L14N-Pad145)") (class "Default")
      (node (ref "U1") (pin "145") (pinfunction "I/O_(D1),_L14N_145") (pintype "bidirectional"))
    )
    (net (code "133") (name "unconnected-(U1A-I{slash}O_(D2),_L15P_YY-Pad141)") (class "Default")
      (node (ref "U1") (pin "141") (pinfunction "I/O_(D2),_L15P_YY_141") (pintype "bidirectional"))
    )
    (net (code "134") (name "unconnected-(U1A-I{slash}O_(D3),_L17N-Pad135)") (class "Default")
      (node (ref "U1") (pin "135") (pinfunction "I/O_(D3),_L17N_135") (pintype "bidirectional"))
    )
    (net (code "135") (name "unconnected-(U1A-I{slash}O_(D4),_L19P-Pad126)") (class "Default")
      (node (ref "U1") (pin "126") (pinfunction "I/O_(D4),_L19P_126") (pintype "bidirectional"))
    )
    (net (code "136") (name "unconnected-(U1A-I{slash}O_(D5),_L21N_YY-Pad120)") (class "Default")
      (node (ref "U1") (pin "120") (pinfunction "I/O_(D5),_L21N_YY_120") (pintype "bidirectional"))
    )
    (net (code "137") (name "unconnected-(U1A-I{slash}O_(D6),_L22P-Pad116)") (class "Default")
      (node (ref "U1") (pin "116") (pinfunction "I/O_(D6),_L22P_116") (pintype "bidirectional"))
    )
    (net (code "138") (name "unconnected-(U1A-I{slash}O_(D7),_L24P_YY-Pad108)") (class "Default")
      (node (ref "U1") (pin "108") (pinfunction "I/O_(D7),_L24P_YY_108") (pintype "bidirectional"))
    )
    (net (code "139") (name "unconnected-(U1A-I{slash}O_(DLL),_L5N-Pad187)") (class "Default")
      (node (ref "U1") (pin "187") (pinfunction "I/O_(DLL),_L5N_187") (pintype "bidirectional"))
    )
    (net (code "140") (name "unconnected-(U1A-I{slash}O_(DLL),_L5P-Pad181)") (class "Default")
      (node (ref "U1") (pin "181") (pinfunction "I/O_(DLL),_L5P_181") (pintype "bidirectional"))
    )
    (net (code "141") (name "unconnected-(U1A-I{slash}O_(DLL),_L31N-Pad75)") (class "Default")
      (node (ref "U1") (pin "75") (pinfunction "I/O_(DLL),_L31N_75") (pintype "bidirectional"))
    )
    (net (code "142") (name "unconnected-(U1A-I{slash}O_(DLL),_L31P-Pad81)") (class "Default")
      (node (ref "U1") (pin "81") (pinfunction "I/O_(DLL),_L31P_81") (pintype "bidirectional"))
    )
    (net (code "143") (name "unconnected-(U1A-I{slash}O_(DOUT,_BUSY),_L12P_YY-Pad154)") (class "Default")
      (node (ref "U1") (pin "154") (pinfunction "I/O_(DOUT,_BUSY),_L12P_YY_154") (pintype "bidirectional"))
    )
    (net (code "144") (name "unconnected-(U1A-I{slash}O_(IRDY),_L18N_YY-Pad132)") (class "Default")
      (node (ref "U1") (pin "132") (pinfunction "I/O_(IRDY),_L18N_YY_132") (pintype "bidirectional"))
    )
    (net (code "145") (name "unconnected-(U1A-I{slash}O_(IRDY),_L44N_YY-Pad24)") (class "Default")
      (node (ref "U1") (pin "24") (pinfunction "I/O_(IRDY),_L44N_YY_24") (pintype "bidirectional"))
    )
    (net (code "146") (name "unconnected-(U1A-I{slash}O_(TRDY)-Pad27)") (class "Default")
      (node (ref "U1") (pin "27") (pinfunction "I/O_(TRDY)_27") (pintype "bidirectional"))
    )
    (net (code "147") (name "unconnected-(U1A-I{slash}O_(TRDY)-Pad129)") (class "Default")
      (node (ref "U1") (pin "129") (pinfunction "I/O_(TRDY)_129") (pintype "bidirectional"))
    )
    (net (code "148") (name "unconnected-(U1A-I{slash}O_(~{CS}),_L11P_YY-Pad160)") (class "Default")
      (node (ref "U1") (pin "160") (pinfunction "I/O_(~{CS}),_L11P_YY_160") (pintype "bidirectional"))
    )
    (net (code "149") (name "unconnected-(U1A-I{slash}O_(~{WRITE}),_L11N_YY-Pad161)") (class "Default")
      (node (ref "U1") (pin "161") (pinfunction "I/O_(~{WRITE}),_L11N_YY_161") (pintype "bidirectional"))
    )
    (net (code "150") (name "unconnected-(U1B-CCLK-Pad155)") (class "Default")
      (node (ref "U1") (pin "155") (pinfunction "CCLK_155") (pintype "bidirectional"))
    )
    (net (code "151") (name "unconnected-(U1B-DIN-Pad153)") (class "Default")
      (node (ref "U1") (pin "153") (pinfunction "DIN_153") (pintype "bidirectional"))
    )
    (net (code "152") (name "unconnected-(U1B-DONE-Pad104)") (class "Default")
      (node (ref "U1") (pin "104") (pinfunction "DONE_104") (pintype "bidirectional"))
    )
    (net (code "153") (name "unconnected-(U1B-M0-Pad52)") (class "Default")
      (node (ref "U1") (pin "52") (pinfunction "M0_52") (pintype "input"))
    )
    (net (code "154") (name "unconnected-(U1B-M1-Pad50)") (class "Default")
      (node (ref "U1") (pin "50") (pinfunction "M1_50") (pintype "input"))
    )
    (net (code "155") (name "unconnected-(U1B-M2-Pad54)") (class "Default")
      (node (ref "U1") (pin "54") (pinfunction "M2_54") (pintype "input"))
    )
    (net (code "156") (name "unconnected-(U1B-PROGRAM-Pad106)") (class "Default")
      (node (ref "U1") (pin "106") (pinfunction "PROGRAM_106") (pintype "input"))
    )
    (net (code "157") (name "unconnected-(U1B-TCK-Pad207)") (class "Default")
      (node (ref "U1") (pin "207") (pinfunction "TCK_207") (pintype "input"))
    )
    (net (code "158") (name "unconnected-(U1B-TDI-Pad159)") (class "Default")
      (node (ref "U1") (pin "159") (pinfunction "TDI_159") (pintype "input"))
    )
    (net (code "159") (name "unconnected-(U1B-TDO-Pad157)") (class "Default")
      (node (ref "U1") (pin "157") (pinfunction "TDO_157") (pintype "output"))
    )
    (net (code "160") (name "unconnected-(U1B-TMS-Pad2)") (class "Default")
      (node (ref "U1") (pin "2") (pinfunction "TMS_2") (pintype "input"))
    )
    (net (code "161") (name "unconnected-(U1B-~{INIT}-Pad107)") (class "Default")
      (node (ref "U1") (pin "107") (pinfunction "~{INIT}_107") (pintype "bidirectional"))
    )
    (net (code "162") (name "unconnected-(U2A-GCK0,_I-Pad80)") (class "Default")
      (node (ref "U2") (pin "80") (pinfunction "GCK0,_I_80") (pintype "input"))
    )
    (net (code "163") (name "unconnected-(U2A-GCK1,_I-Pad77)") (class "Default")
      (node (ref "U2") (pin "77") (pinfunction "GCK1,_I_77") (pintype "input"))
    )
    (net (code "164") (name "unconnected-(U2A-GCK2,_I-Pad182)") (class "Default")
      (node (ref "U2") (pin "182") (pinfunction "GCK2,_I_182") (pintype "input"))
    )
    (net (code "165") (name "unconnected-(U2A-GCK3,_I-Pad185)") (class "Default")
      (node (ref "U2") (pin "185") (pinfunction "GCK3,_I_185") (pintype "input"))
    )
    (net (code "166") (name "unconnected-(U2A-I{slash}O,_L0P_YY-Pad202)") (class "Default")
      (node (ref "U2") (pin "202") (pinfunction "I/O,_L0P_YY_202") (pintype "bidirectional"))
    )
    (net (code "167") (name "unconnected-(U2A-I{slash}O,_L1P_Y-Pad198)") (class "Default")
      (node (ref "U2") (pin "198") (pinfunction "I/O,_L1P_Y_198") (pintype "bidirectional"))
    )
    (net (code "168") (name "unconnected-(U2A-I{slash}O,_L2N_Y-Pad194)") (class "Default")
      (node (ref "U2") (pin "194") (pinfunction "I/O,_L2N_Y_194") (pintype "bidirectional"))
    )
    (net (code "169") (name "unconnected-(U2A-I{slash}O,_L2P_Y-Pad193)") (class "Default")
      (node (ref "U2") (pin "193") (pinfunction "I/O,_L2P_Y_193") (pintype "bidirectional"))
    )
    (net (code "170") (name "unconnected-(U2A-I{slash}O,_L3N_Y-Pad192)") (class "Default")
      (node (ref "U2") (pin "192") (pinfunction "I/O,_L3N_Y_192") (pintype "bidirectional"))
    )
    (net (code "171") (name "unconnected-(U2A-I{slash}O,_L3P_Y-Pad191)") (class "Default")
      (node (ref "U2") (pin "191") (pinfunction "I/O,_L3P_Y_191") (pintype "bidirectional"))
    )
    (net (code "172") (name "unconnected-(U2A-I{slash}O,_L4P_Y-Pad188)") (class "Default")
      (node (ref "U2") (pin "188") (pinfunction "I/O,_L4P_Y_188") (pintype "bidirectional"))
    )
    (net (code "173") (name "unconnected-(U2A-I{slash}O,_L6N_Y-Pad179)") (class "Default")
      (node (ref "U2") (pin "179") (pinfunction "I/O,_L6N_Y_179") (pintype "bidirectional"))
    )
    (net (code "174") (name "unconnected-(U2A-I{slash}O,_L7N_Y-Pad176)") (class "Default")
      (node (ref "U2") (pin "176") (pinfunction "I/O,_L7N_Y_176") (pintype "bidirectional"))
    )
    (net (code "175") (name "unconnected-(U2A-I{slash}O,_L7P_Y-Pad175)") (class "Default")
      (node (ref "U2") (pin "175") (pinfunction "I/O,_L7P_Y_175") (pintype "bidirectional"))
    )
    (net (code "176") (name "unconnected-(U2A-I{slash}O,_L8N_Y-Pad174)") (class "Default")
      (node (ref "U2") (pin "174") (pinfunction "I/O,_L8N_Y_174") (pintype "bidirectional"))
    )
    (net (code "177") (name "unconnected-(U2A-I{slash}O,_L8P_Y-Pad173)") (class "Default")
      (node (ref "U2") (pin "173") (pinfunction "I/O,_L8P_Y_173") (pintype "bidirectional"))
    )
    (net (code "178") (name "unconnected-(U2A-I{slash}O,_L9N_Y-Pad169)") (class "Default")
      (node (ref "U2") (pin "169") (pinfunction "I/O,_L9N_Y_169") (pintype "bidirectional"))
    )
    (net (code "179") (name "unconnected-(U2A-I{slash}O,_L10N_YY-Pad165)") (class "Default")
      (node (ref "U2") (pin "165") (pinfunction "I/O,_L10N_YY_165") (pintype "bidirectional"))
    )
    (net (code "180") (name "unconnected-(U2A-I{slash}O,_L13P-Pad151)") (class "Default")
      (node (ref "U2") (pin "151") (pinfunction "I/O,_L13P_151") (pintype "bidirectional"))
    )
    (net (code "181") (name "unconnected-(U2A-I{slash}O,_L15N_YY-Pad140)") (class "Default")
      (node (ref "U2") (pin "140") (pinfunction "I/O,_L15N_YY_140") (pintype "bidirectional"))
    )
    (net (code "182") (name "unconnected-(U2A-I{slash}O,_L16N_YY-Pad138)") (class "Default")
      (node (ref "U2") (pin "138") (pinfunction "I/O,_L16N_YY_138") (pintype "bidirectional"))
    )
    (net (code "183") (name "unconnected-(U2A-I{slash}O,_L16P_YY-Pad139)") (class "Default")
      (node (ref "U2") (pin "139") (pinfunction "I/O,_L16P_YY_139") (pintype "bidirectional"))
    )
    (net (code "184") (name "unconnected-(U2A-I{slash}O,_L18P_YY-Pad133)") (class "Default")
      (node (ref "U2") (pin "133") (pinfunction "I/O,_L18P_YY_133") (pintype "bidirectional"))
    )
    (net (code "185") (name "unconnected-(U2A-I{slash}O,_L20N_YY-Pad122)") (class "Default")
      (node (ref "U2") (pin "122") (pinfunction "I/O,_L20N_YY_122") (pintype "bidirectional"))
    )
    (net (code "186") (name "unconnected-(U2A-I{slash}O,_L20P_YY-Pad123)") (class "Default")
      (node (ref "U2") (pin "123") (pinfunction "I/O,_L20P_YY_123") (pintype "bidirectional"))
    )
    (net (code "187") (name "unconnected-(U2A-I{slash}O,_L21P_YY-Pad121)") (class "Default")
      (node (ref "U2") (pin "121") (pinfunction "I/O,_L21P_YY_121") (pintype "bidirectional"))
    )
    (net (code "188") (name "unconnected-(U2A-I{slash}O,_L23P_Y-Pad112)") (class "Default")
      (node (ref "U2") (pin "112") (pinfunction "I/O,_L23P_Y_112") (pintype "bidirectional"))
    )
    (net (code "189") (name "unconnected-(U2A-I{slash}O,_L25N_YY-Pad101)") (class "Default")
      (node (ref "U2") (pin "101") (pinfunction "I/O,_L25N_YY_101") (pintype "bidirectional"))
    )
    (net (code "190") (name "unconnected-(U2A-I{slash}O,_L25P_YY-Pad102)") (class "Default")
      (node (ref "U2") (pin "102") (pinfunction "I/O,_L25P_YY_102") (pintype "bidirectional"))
    )
    (net (code "191") (name "unconnected-(U2A-I{slash}O,_L26N_YY-Pad97)") (class "Default")
      (node (ref "U2") (pin "97") (pinfunction "I/O,_L26N_YY_97") (pintype "bidirectional"))
    )
    (net (code "192") (name "unconnected-(U2A-I{slash}O,_L27N_Y-Pad93)") (class "Default")
      (node (ref "U2") (pin "93") (pinfunction "I/O,_L27N_Y_93") (pintype "bidirectional"))
    )
    (net (code "193") (name "unconnected-(U2A-I{slash}O,_L28N_Y-Pad88)") (class "Default")
      (node (ref "U2") (pin "88") (pinfunction "I/O,_L28N_Y_88") (pintype "bidirectional"))
    )
    (net (code "194") (name "unconnected-(U2A-I{slash}O,_L28P_Y-Pad89)") (class "Default")
      (node (ref "U2") (pin "89") (pinfunction "I/O,_L28P_Y_89") (pintype "bidirectional"))
    )
    (net (code "195") (name "unconnected-(U2A-I{slash}O,_L29N_Y-Pad86)") (class "Default")
      (node (ref "U2") (pin "86") (pinfunction "I/O,_L29N_Y_86") (pintype "bidirectional"))
    )
    (net (code "196") (name "unconnected-(U2A-I{slash}O,_L29P_Y-Pad87)") (class "Default")
      (node (ref "U2") (pin "87") (pinfunction "I/O,_L29P_Y_87") (pintype "bidirectional"))
    )
    (net (code "197") (name "unconnected-(U2A-I{slash}O,_L30N_Y-Pad83)") (class "Default")
      (node (ref "U2") (pin "83") (pinfunction "I/O,_L30N_Y_83") (pintype "bidirectional"))
    )
    (net (code "198") (name "unconnected-(U2A-I{slash}O,_L32N-Pad71)") (class "Default")
      (node (ref "U2") (pin "71") (pinfunction "I/O,_L32N_71") (pintype "bidirectional"))
    )
    (net (code "199") (name "unconnected-(U2A-I{slash}O,_L33N_Y-Pad68)") (class "Default")
      (node (ref "U2") (pin "68") (pinfunction "I/O,_L33N_Y_68") (pintype "bidirectional"))
    )
    (net (code "200") (name "unconnected-(U2A-I{slash}O,_L33P_Y-Pad69)") (class "Default")
      (node (ref "U2") (pin "69") (pinfunction "I/O,_L33P_Y_69") (pintype "bidirectional"))
    )
    (net (code "201") (name "unconnected-(U2A-I{slash}O,_L34P_Y-Pad64)") (class "Default")
      (node (ref "U2") (pin "64") (pinfunction "I/O,_L34P_Y_64") (pintype "bidirectional"))
    )
    (net (code "202") (name "unconnected-(U2A-I{slash}O,_L35N-Pad61)") (class "Default")
      (node (ref "U2") (pin "61") (pinfunction "I/O,_L35N_61") (pintype "bidirectional"))
    )
    (net (code "203") (name "unconnected-(U2A-I{slash}O,_L35P-Pad62)") (class "Default")
      (node (ref "U2") (pin "62") (pinfunction "I/O,_L35P_62") (pintype "bidirectional"))
    )
    (net (code "204") (name "unconnected-(U2A-I{slash}O,_L36P_YY-Pad60)") (class "Default")
      (node (ref "U2") (pin "60") (pinfunction "I/O,_L36P_YY_60") (pintype "bidirectional"))
    )
    (net (code "205") (name "unconnected-(U2A-I{slash}O,_L37N_YY-Pad55)") (class "Default")
      (node (ref "U2") (pin "55") (pinfunction "I/O,_L37N_YY_55") (pintype "bidirectional"))
    )
    (net (code "206") (name "unconnected-(U2A-I{slash}O,_L37P_YY-Pad56)") (class "Default")
      (node (ref "U2") (pin "56") (pinfunction "I/O,_L37P_YY_56") (pintype "bidirectional"))
    )
    (net (code "207") (name "unconnected-(U2A-I{slash}O,_L38N_YY-Pad49)") (class "Default")
      (node (ref "U2") (pin "49") (pinfunction "I/O,_L38N_YY_49") (pintype "bidirectional"))
    )
    (net (code "208") (name "unconnected-(U2A-I{slash}O,_L38P_YY-Pad48)") (class "Default")
      (node (ref "U2") (pin "48") (pinfunction "I/O,_L38P_YY_48") (pintype "bidirectional"))
    )
    (net (code "209") (name "unconnected-(U2A-I{slash}O,_L39N-Pad46)") (class "Default")
      (node (ref "U2") (pin "46") (pinfunction "I/O,_L39N_46") (pintype "bidirectional"))
    )
    (net (code "210") (name "unconnected-(U2A-I{slash}O,_L40P-Pad40)") (class "Default")
      (node (ref "U2") (pin "40") (pinfunction "I/O,_L40P_40") (pintype "bidirectional"))
    )
    (net (code "211") (name "unconnected-(U2A-I{slash}O,_L41N_YY-Pad36)") (class "Default")
      (node (ref "U2") (pin "36") (pinfunction "I/O,_L41N_YY_36") (pintype "bidirectional"))
    )
    (net (code "212") (name "unconnected-(U2A-I{slash}O,_L41P_YY-Pad35)") (class "Default")
      (node (ref "U2") (pin "35") (pinfunction "I/O,_L41P_YY_35") (pintype "bidirectional"))
    )
    (net (code "213") (name "unconnected-(U2A-I{slash}O,_L43P-Pad30)") (class "Default")
      (node (ref "U2") (pin "30") (pinfunction "I/O,_L43P_30") (pintype "bidirectional"))
    )
    (net (code "214") (name "unconnected-(U2A-I{slash}O,_L44P_YY-Pad23)") (class "Default")
      (node (ref "U2") (pin "23") (pinfunction "I/O,_L44P_YY_23") (pintype "bidirectional"))
    )
    (net (code "215") (name "unconnected-(U2A-I{slash}O,_L45N-Pad21)") (class "Default")
      (node (ref "U2") (pin "21") (pinfunction "I/O,_L45N_21") (pintype "bidirectional"))
    )
    (net (code "216") (name "unconnected-(U2A-I{slash}O,_L46N_YY-Pad18)") (class "Default")
      (node (ref "U2") (pin "18") (pinfunction "I/O,_L46N_YY_18") (pintype "bidirectional"))
    )
    (net (code "217") (name "unconnected-(U2A-I{slash}O,_L46P_YY-Pad17)") (class "Default")
      (node (ref "U2") (pin "17") (pinfunction "I/O,_L46P_YY_17") (pintype "bidirectional"))
    )
    (net (code "218") (name "unconnected-(U2A-I{slash}O,_L47N_YY-Pad16)") (class "Default")
      (node (ref "U2") (pin "16") (pinfunction "I/O,_L47N_YY_16") (pintype "bidirectional"))
    )
    (net (code "219") (name "unconnected-(U2A-I{slash}O,_L47P_YY-Pad15)") (class "Default")
      (node (ref "U2") (pin "15") (pinfunction "I/O,_L47P_YY_15") (pintype "bidirectional"))
    )
    (net (code "220") (name "unconnected-(U2A-I{slash}O,_L48N-Pad11)") (class "Default")
      (node (ref "U2") (pin "11") (pinfunction "I/O,_L48N_11") (pintype "bidirectional"))
    )
    (net (code "221") (name "unconnected-(U2A-I{slash}O,_L49N_Y-Pad7)") (class "Default")
      (node (ref "U2") (pin "7") (pinfunction "I/O,_L49N_Y_7") (pintype "bidirectional"))
    )
    (net (code "222") (name "unconnected-(U2A-I{slash}O,_VREF_0,_L0N_YY-Pad203)") (class "Default")
      (node (ref "U2") (pin "203") (pinfunction "I/O,_VREF_0,_L0N_YY_203") (pintype "bidirectional"))
    )
    (net (code "223") (name "unconnected-(U2A-I{slash}O,_VREF_0,_L1N_Y-Pad199)") (class "Default")
      (node (ref "U2") (pin "199") (pinfunction "I/O,_VREF_0,_L1N_Y_199") (pintype "bidirectional"))
    )
    (net (code "224") (name "unconnected-(U2A-I{slash}O,_VREF_0,_L4N_Y-Pad189)") (class "Default")
      (node (ref "U2") (pin "189") (pinfunction "I/O,_VREF_0,_L4N_Y_189") (pintype "bidirectional"))
    )
    (net (code "225") (name "unconnected-(U2A-I{slash}O,_VREF_0-Pad205)") (class "Default")
      (node (ref "U2") (pin "205") (pinfunction "I/O,_VREF_0_205") (pintype "bidirectional"))
    )
    (net (code "226") (name "unconnected-(U2A-I{slash}O,_VREF_1,_L6P_Y-Pad178)") (class "Default")
      (node (ref "U2") (pin "178") (pinfunction "I/O,_VREF_1,_L6P_Y_178") (pintype "bidirectional"))
    )
    (net (code "227") (name "unconnected-(U2A-I{slash}O,_VREF_1,_L9P_Y-Pad168)") (class "Default")
      (node (ref "U2") (pin "168") (pinfunction "I/O,_VREF_1,_L9P_Y_168") (pintype "bidirectional"))
    )
    (net (code "228") (name "unconnected-(U2A-I{slash}O,_VREF_1,_L10P_YY-Pad164)") (class "Default")
      (node (ref "U2") (pin "164") (pinfunction "I/O,_VREF_1,_L10P_YY_164") (pintype "bidirectional"))
    )
    (net (code "229") (name "unconnected-(U2A-I{slash}O,_VREF_1-Pad162)") (class "Default")
      (node (ref "U2") (pin "162") (pinfunction "I/O,_VREF_1_162") (pintype "bidirectional"))
    )
    (net (code "230") (name "unconnected-(U2A-I{slash}O,_VREF_2,_L13N-Pad150)") (class "Default")
      (node (ref "U2") (pin "150") (pinfunction "I/O,_VREF_2,_L13N_150") (pintype "bidirectional"))
    )
    (net (code "231") (name "unconnected-(U2A-I{slash}O,_VREF_2,_L14P-Pad146)") (class "Default")
      (node (ref "U2") (pin "146") (pinfunction "I/O,_VREF_2,_L14P_146") (pintype "bidirectional"))
    )
    (net (code "232") (name "unconnected-(U2A-I{slash}O,_VREF_2,_L17P-Pad136)") (class "Default")
      (node (ref "U2") (pin "136") (pinfunction "I/O,_VREF_2,_L17P_136") (pintype "bidirectional"))
    )
    (net (code "233") (name "unconnected-(U2A-I{slash}O,_VREF_2-Pad152)") (class "Default")
      (node (ref "U2") (pin "152") (pinfunction "I/O,_VREF_2_152") (pintype "bidirectional"))
    )
    (net (code "234") (name "unconnected-(U2A-I{slash}O,_VREF_3,_L19N-Pad125)") (class "Default")
      (node (ref "U2") (pin "125") (pinfunction "I/O,_VREF_3,_L19N_125") (pintype "bidirectional"))
    )
    (net (code "235") (name "unconnected-(U2A-I{slash}O,_VREF_3,_L22N-Pad115)") (class "Default")
      (node (ref "U2") (pin "115") (pinfunction "I/O,_VREF_3,_L22N_115") (pintype "bidirectional"))
    )
    (net (code "236") (name "unconnected-(U2A-I{slash}O,_VREF_3,_L23N_Y-Pad111)") (class "Default")
      (node (ref "U2") (pin "111") (pinfunction "I/O,_VREF_3,_L23N_Y_111") (pintype "bidirectional"))
    )
    (net (code "237") (name "unconnected-(U2A-I{slash}O,_VREF_3-Pad109)") (class "Default")
      (node (ref "U2") (pin "109") (pinfunction "I/O,_VREF_3_109") (pintype "bidirectional"))
    )
    (net (code "238") (name "unconnected-(U2A-I{slash}O,_VREF_4,_L26P_YY-Pad98)") (class "Default")
      (node (ref "U2") (pin "98") (pinfunction "I/O,_VREF_4,_L26P_YY_98") (pintype "bidirectional"))
    )
    (net (code "239") (name "unconnected-(U2A-I{slash}O,_VREF_4,_L27P_Y-Pad94)") (class "Default")
      (node (ref "U2") (pin "94") (pinfunction "I/O,_VREF_4,_L27P_Y_94") (pintype "bidirectional"))
    )
    (net (code "240") (name "unconnected-(U2A-I{slash}O,_VREF_4,_L30P_Y-Pad84)") (class "Default")
      (node (ref "U2") (pin "84") (pinfunction "I/O,_VREF_4,_L30P_Y_84") (pintype "bidirectional"))
    )
    (net (code "241") (name "unconnected-(U2A-I{slash}O,_VREF_4-Pad100)") (class "Default")
      (node (ref "U2") (pin "100") (pinfunction "I/O,_VREF_4_100") (pintype "bidirectional"))
    )
    (net (code "242") (name "unconnected-(U2A-I{slash}O,_VREF_5,_L32P-Pad73)") (class "Default")
      (node (ref "U2") (pin "73") (pinfunction "I/O,_VREF_5,_L32P_73") (pintype "bidirectional"))
    )
    (net (code "243") (name "unconnected-(U2A-I{slash}O,_VREF_5,_L34N_Y-Pad63)") (class "Default")
      (node (ref "U2") (pin "63") (pinfunction "I/O,_VREF_5,_L34N_Y_63") (pintype "bidirectional"))
    )
    (net (code "244") (name "unconnected-(U2A-I{slash}O,_VREF_5,_L36N_YY-Pad59)") (class "Default")
      (node (ref "U2") (pin "59") (pinfunction "I/O,_VREF_5,_L36N_YY_59") (pintype "bidirectional"))
    )
    (net (code "245") (name "unconnected-(U2A-I{slash}O,_VREF_5-Pad57)") (class "Default")
      (node (ref "U2") (pin "57") (pinfunction "I/O,_VREF_5_57") (pintype "bidirectional"))
    )
    (net (code "246") (name "unconnected-(U2A-I{slash}O,_VREF_6,_L39P-Pad45)") (class "Default")
      (node (ref "U2") (pin "45") (pinfunction "I/O,_VREF_6,_L39P_45") (pintype "bidirectional"))
    )
    (net (code "247") (name "unconnected-(U2A-I{slash}O,_VREF_6,_L40N-Pad41)") (class "Default")
      (node (ref "U2") (pin "41") (pinfunction "I/O,_VREF_6,_L40N_41") (pintype "bidirectional"))
    )
    (net (code "248") (name "unconnected-(U2A-I{slash}O,_VREF_6,_L43N-Pad31)") (class "Default")
      (node (ref "U2") (pin "31") (pinfunction "I/O,_VREF_6,_L43N_31") (pintype "bidirectional"))
    )
    (net (code "249") (name "unconnected-(U2A-I{slash}O,_VREF_6-Pad47)") (class "Default")
      (node (ref "U2") (pin "47") (pinfunction "I/O,_VREF_6_47") (pintype "bidirectional"))
    )
    (net (code "250") (name "unconnected-(U2A-I{slash}O,_VREF_7,_L45P-Pad20)") (class "Default")
      (node (ref "U2") (pin "20") (pinfunction "I/O,_VREF_7,_L45P_20") (pintype "bidirectional"))
    )
    (net (code "251") (name "unconnected-(U2A-I{slash}O,_VREF_7,_L48P-Pad10)") (class "Default")
      (node (ref "U2") (pin "10") (pinfunction "I/O,_VREF_7,_L48P_10") (pintype "bidirectional"))
    )
    (net (code "252") (name "unconnected-(U2A-I{slash}O,_VREF_7,_L49P_Y-Pad6)") (class "Default")
      (node (ref "U2") (pin "6") (pinfunction "I/O,_VREF_7,_L49P_Y_6") (pintype "bidirectional"))
    )
    (net (code "253") (name "unconnected-(U2A-I{slash}O,_VREF_7-Pad4)") (class "Default")
      (node (ref "U2") (pin "4") (pinfunction "I/O,_VREF_7_4") (pintype "bidirectional"))
    )
    (net (code "254") (name "unconnected-(U2A-I{slash}O-Pad3)") (class "Default")
      (node (ref "U2") (pin "3") (pinfunction "I/O_3") (pintype "bidirectional"))
    )
    (net (code "255") (name "unconnected-(U2A-I{slash}O-Pad5)") (class "Default")
      (node (ref "U2") (pin "5") (pinfunction "I/O_5") (pintype "bidirectional"))
    )
    (net (code "256") (name "unconnected-(U2A-I{slash}O-Pad8)") (class "Default")
      (node (ref "U2") (pin "8") (pinfunction "I/O_8") (pintype "bidirectional"))
    )
    (net (code "257") (name "unconnected-(U2A-I{slash}O-Pad9)") (class "Default")
      (node (ref "U2") (pin "9") (pinfunction "I/O_9") (pintype "bidirectional"))
    )
    (net (code "258") (name "unconnected-(U2A-I{slash}O-Pad22)") (class "Default")
      (node (ref "U2") (pin "22") (pinfunction "I/O_22") (pintype "bidirectional"))
    )
    (net (code "259") (name "unconnected-(U2A-I{slash}O-Pad29)") (class "Default")
      (node (ref "U2") (pin "29") (pinfunction "I/O_29") (pintype "bidirectional"))
    )
    (net (code "260") (name "unconnected-(U2A-I{slash}O-Pad42)") (class "Default")
      (node (ref "U2") (pin "42") (pinfunction "I/O_42") (pintype "bidirectional"))
    )
    (net (code "261") (name "unconnected-(U2A-I{slash}O-Pad43)") (class "Default")
      (node (ref "U2") (pin "43") (pinfunction "I/O_43") (pintype "bidirectional"))
    )
    (net (code "262") (name "unconnected-(U2A-I{slash}O-Pad44)") (class "Default")
      (node (ref "U2") (pin "44") (pinfunction "I/O_44") (pintype "bidirectional"))
    )
    (net (code "263") (name "unconnected-(U2A-I{slash}O-Pad58)") (class "Default")
      (node (ref "U2") (pin "58") (pinfunction "I/O_58") (pintype "bidirectional"))
    )
    (net (code "264") (name "unconnected-(U2A-I{slash}O-Pad70)") (class "Default")
      (node (ref "U2") (pin "70") (pinfunction "I/O_70") (pintype "bidirectional"))
    )
    (net (code "265") (name "unconnected-(U2A-I{slash}O-Pad74)") (class "Default")
      (node (ref "U2") (pin "74") (pinfunction "I/O_74") (pintype "bidirectional"))
    )
    (net (code "266") (name "unconnected-(U2A-I{slash}O-Pad82)") (class "Default")
      (node (ref "U2") (pin "82") (pinfunction "I/O_82") (pintype "bidirectional"))
    )
    (net (code "267") (name "unconnected-(U2A-I{slash}O-Pad95)") (class "Default")
      (node (ref "U2") (pin "95") (pinfunction "I/O_95") (pintype "bidirectional"))
    )
    (net (code "268") (name "unconnected-(U2A-I{slash}O-Pad96)") (class "Default")
      (node (ref "U2") (pin "96") (pinfunction "I/O_96") (pintype "bidirectional"))
    )
    (net (code "269") (name "unconnected-(U2A-I{slash}O-Pad99)") (class "Default")
      (node (ref "U2") (pin "99") (pinfunction "I/O_99") (pintype "bidirectional"))
    )
    (net (code "270") (name "unconnected-(U2A-I{slash}O-Pad110)") (class "Default")
      (node (ref "U2") (pin "110") (pinfunction "I/O_110") (pintype "bidirectional"))
    )
    (net (code "271") (name "unconnected-(U2A-I{slash}O-Pad113)") (class "Default")
      (node (ref "U2") (pin "113") (pinfunction "I/O_113") (pintype "bidirectional"))
    )
    (net (code "272") (name "unconnected-(U2A-I{slash}O-Pad114)") (class "Default")
      (node (ref "U2") (pin "114") (pinfunction "I/O_114") (pintype "bidirectional"))
    )
    (net (code "273") (name "unconnected-(U2A-I{slash}O-Pad127)") (class "Default")
      (node (ref "U2") (pin "127") (pinfunction "I/O_127") (pintype "bidirectional"))
    )
    (net (code "274") (name "unconnected-(U2A-I{slash}O-Pad134)") (class "Default")
      (node (ref "U2") (pin "134") (pinfunction "I/O_134") (pintype "bidirectional"))
    )
    (net (code "275") (name "unconnected-(U2A-I{slash}O-Pad147)") (class "Default")
      (node (ref "U2") (pin "147") (pinfunction "I/O_147") (pintype "bidirectional"))
    )
    (net (code "276") (name "unconnected-(U2A-I{slash}O-Pad148)") (class "Default")
      (node (ref "U2") (pin "148") (pinfunction "I/O_148") (pintype "bidirectional"))
    )
    (net (code "277") (name "unconnected-(U2A-I{slash}O-Pad149)") (class "Default")
      (node (ref "U2") (pin "149") (pinfunction "I/O_149") (pintype "bidirectional"))
    )
    (net (code "278") (name "unconnected-(U2A-I{slash}O-Pad163)") (class "Default")
      (node (ref "U2") (pin "163") (pinfunction "I/O_163") (pintype "bidirectional"))
    )
    (net (code "279") (name "unconnected-(U2A-I{slash}O-Pad166)") (class "Default")
      (node (ref "U2") (pin "166") (pinfunction "I/O_166") (pintype "bidirectional"))
    )
    (net (code "280") (name "unconnected-(U2A-I{slash}O-Pad167)") (class "Default")
      (node (ref "U2") (pin "167") (pinfunction "I/O_167") (pintype "bidirectional"))
    )
    (net (code "281") (name "unconnected-(U2A-I{slash}O-Pad180)") (class "Default")
      (node (ref "U2") (pin "180") (pinfunction "I/O_180") (pintype "bidirectional"))
    )
    (net (code "282") (name "unconnected-(U2A-I{slash}O-Pad200)") (class "Default")
      (node (ref "U2") (pin "200") (pinfunction "I/O_200") (pintype "bidirectional"))
    )
    (net (code "283") (name "unconnected-(U2A-I{slash}O-Pad201)") (class "Default")
      (node (ref "U2") (pin "201") (pinfunction "I/O_201") (pintype "bidirectional"))
    )
    (net (code "284") (name "unconnected-(U2A-I{slash}O-Pad204)") (class "Default")
      (node (ref "U2") (pin "204") (pinfunction "I/O_204") (pintype "bidirectional"))
    )
    (net (code "285") (name "unconnected-(U2A-I{slash}O-Pad206)") (class "Default")
      (node (ref "U2") (pin "206") (pinfunction "I/O_206") (pintype "bidirectional"))
    )
    (net (code "286") (name "unconnected-(U2A-I{slash}O_(D1),_L14N-Pad145)") (class "Default")
      (node (ref "U2") (pin "145") (pinfunction "I/O_(D1),_L14N_145") (pintype "bidirectional"))
    )
    (net (code "287") (name "unconnected-(U2A-I{slash}O_(D2),_L15P_YY-Pad141)") (class "Default")
      (node (ref "U2") (pin "141") (pinfunction "I/O_(D2),_L15P_YY_141") (pintype "bidirectional"))
    )
    (net (code "288") (name "unconnected-(U2A-I{slash}O_(D3),_L17N-Pad135)") (class "Default")
      (node (ref "U2") (pin "135") (pinfunction "I/O_(D3),_L17N_135") (pintype "bidirectional"))
    )
    (net (code "289") (name "unconnected-(U2A-I{slash}O_(D4),_L19P-Pad126)") (class "Default")
      (node (ref "U2") (pin "126") (pinfunction "I/O_(D4),_L19P_126") (pintype "bidirectional"))
    )
    (net (code "290") (name "unconnected-(U2A-I{slash}O_(D5),_L21N_YY-Pad120)") (class "Default")
      (node (ref "U2") (pin "120") (pinfunction "I/O_(D5),_L21N_YY_120") (pintype "bidirectional"))
    )
    (net (code "291") (name "unconnected-(U2A-I{slash}O_(D6),_L22P-Pad116)") (class "Default")
      (node (ref "U2") (pin "116") (pinfunction "I/O_(D6),_L22P_116") (pintype "bidirectional"))
    )
    (net (code "292") (name "unconnected-(U2A-I{slash}O_(D7),_L24P_YY-Pad108)") (class "Default")
      (node (ref "U2") (pin "108") (pinfunction "I/O_(D7),_L24P_YY_108") (pintype "bidirectional"))
    )
    (net (code "293") (name "unconnected-(U2A-I{slash}O_(DLL),_L5N-Pad187)") (class "Default")
      (node (ref "U2") (pin "187") (pinfunction "I/O_(DLL),_L5N_187") (pintype "bidirectional"))
    )
    (net (code "294") (name "unconnected-(U2A-I{slash}O_(DLL),_L5P-Pad181)") (class "Default")
      (node (ref "U2") (pin "181") (pinfunction "I/O_(DLL),_L5P_181") (pintype "bidirectional"))
    )
    (net (code "295") (name "unconnected-(U2A-I{slash}O_(DLL),_L31N-Pad75)") (class "Default")
      (node (ref "U2") (pin "75") (pinfunction "I/O_(DLL),_L31N_75") (pintype "bidirectional"))
    )
    (net (code "296") (name "unconnected-(U2A-I{slash}O_(DLL),_L31P-Pad81)") (class "Default")
      (node (ref "U2") (pin "81") (pinfunction "I/O_(DLL),_L31P_81") (pintype "bidirectional"))
    )
    (net (code "297") (name "unconnected-(U2A-I{slash}O_(DOUT,_BUSY),_L12P_YY-Pad154)") (class "Default")
      (node (ref "U2") (pin "154") (pinfunction "I/O_(DOUT,_BUSY),_L12P_YY_154") (pintype "bidirectional"))
    )
    (net (code "298") (name "unconnected-(U2A-I{slash}O_(IRDY),_L18N_YY-Pad132)") (class "Default")
      (node (ref "U2") (pin "132") (pinfunction "I/O_(IRDY),_L18N_YY_132") (pintype "bidirectional"))
    )
    (net (code "299") (name "unconnected-(U2A-I{slash}O_(IRDY),_L44N_YY-Pad24)") (class "Default")
      (node (ref "U2") (pin "24") (pinfunction "I/O_(IRDY),_L44N_YY_24") (pintype "bidirectional"))
    )
    (net (code "300") (name "unconnected-(U2A-I{slash}O_(TRDY)-Pad27)") (class "Default")
      (node (ref "U2") (pin "27") (pinfunction "I/O_(TRDY)_27") (pintype "bidirectional"))
    )
    (net (code "301") (name "unconnected-(U2A-I{slash}O_(TRDY)-Pad129)") (class "Default")
      (node (ref "U2") (pin "129") (pinfunction "I/O_(TRDY)_129") (pintype "bidirectional"))
    )
    (net (code "302") (name "unconnected-(U2A-I{slash}O_(~{CS}),_L11P_YY-Pad160)") (class "Default")
      (node (ref "U2") (pin "160") (pinfunction "I/O_(~{CS}),_L11P_YY_160") (pintype "bidirectional"))
    )
    (net (code "303") (name "unconnected-(U2A-I{slash}O_(~{WRITE}),_L11N_YY-Pad161)") (class "Default")
      (node (ref "U2") (pin "161") (pinfunction "I/O_(~{WRITE}),_L11N_YY_161") (pintype "bidirectional"))
    )
    (net (code "304") (name "unconnected-(U2B-CCLK-Pad155)") (class "Default")
      (node (ref "U2") (pin "155") (pinfunction "CCLK_155") (pintype "bidirectional"))
    )
    (net (code "305") (name "unconnected-(U2B-DIN-Pad153)") (class "Default")
      (node (ref "U2") (pin "153") (pinfunction "DIN_153") (pintype "bidirectional"))
    )
    (net (code "306") (name "unconnected-(U2B-DONE-Pad104)") (class "Default")
      (node (ref "U2") (pin "104") (pinfunction "DONE_104") (pintype "bidirectional"))
    )
    (net (code "307") (name "unconnected-(U2B-M0-Pad52)") (class "Default")
      (node (ref "U2") (pin "52") (pinfunction "M0_52") (pintype "input"))
    )
    (net (code "308") (name "unconnected-(U2B-M1-Pad50)") (class "Default")
      (node (ref "U2") (pin "50") (pinfunction "M1_50") (pintype "input"))
    )
    (net (code "309") (name "unconnected-(U2B-M2-Pad54)") (class "Default")
      (node (ref "U2") (pin "54") (pinfunction "M2_54") (pintype "input"))
    )
    (net (code "310") (name "unconnected-(U2B-PROGRAM-Pad106)") (class "Default")
      (node (ref "U2") (pin "106") (pinfunction "PROGRAM_106") (pintype "input"))
    )
    (net (code "311") (name "unconnected-(U2B-TCK-Pad207)") (class "Default")
      (node (ref "U2") (pin "207") (pinfunction "TCK_207") (pintype "input"))
    )
    (net (code "312") (name "unconnected-(U2B-TDI-Pad159)") (class "Default")
      (node (ref "U2") (pin "159") (pinfunction "TDI_159") (pintype "input"))
    )
    (net (code "313") (name "unconnected-(U2B-TDO-Pad157)") (class "Default")
      (node (ref "U2") (pin "157") (pinfunction "TDO_157") (pintype "output"))
    )
    (net (code "314") (name "unconnected-(U2B-TMS-Pad2)") (class "Default")
      (node (ref "U2") (pin "2") (pinfunction "TMS_2") (pintype "input"))
    )
    (net (code "315") (name "unconnected-(U2B-~{INIT}-Pad107)") (class "Default")
      (node (ref "U2") (pin "107") (pinfunction "~{INIT}_107") (pintype "bidirectional"))
    )
  )
)
